# SCH.net
KiCad netlist of a schematic drawn in Altium Designer
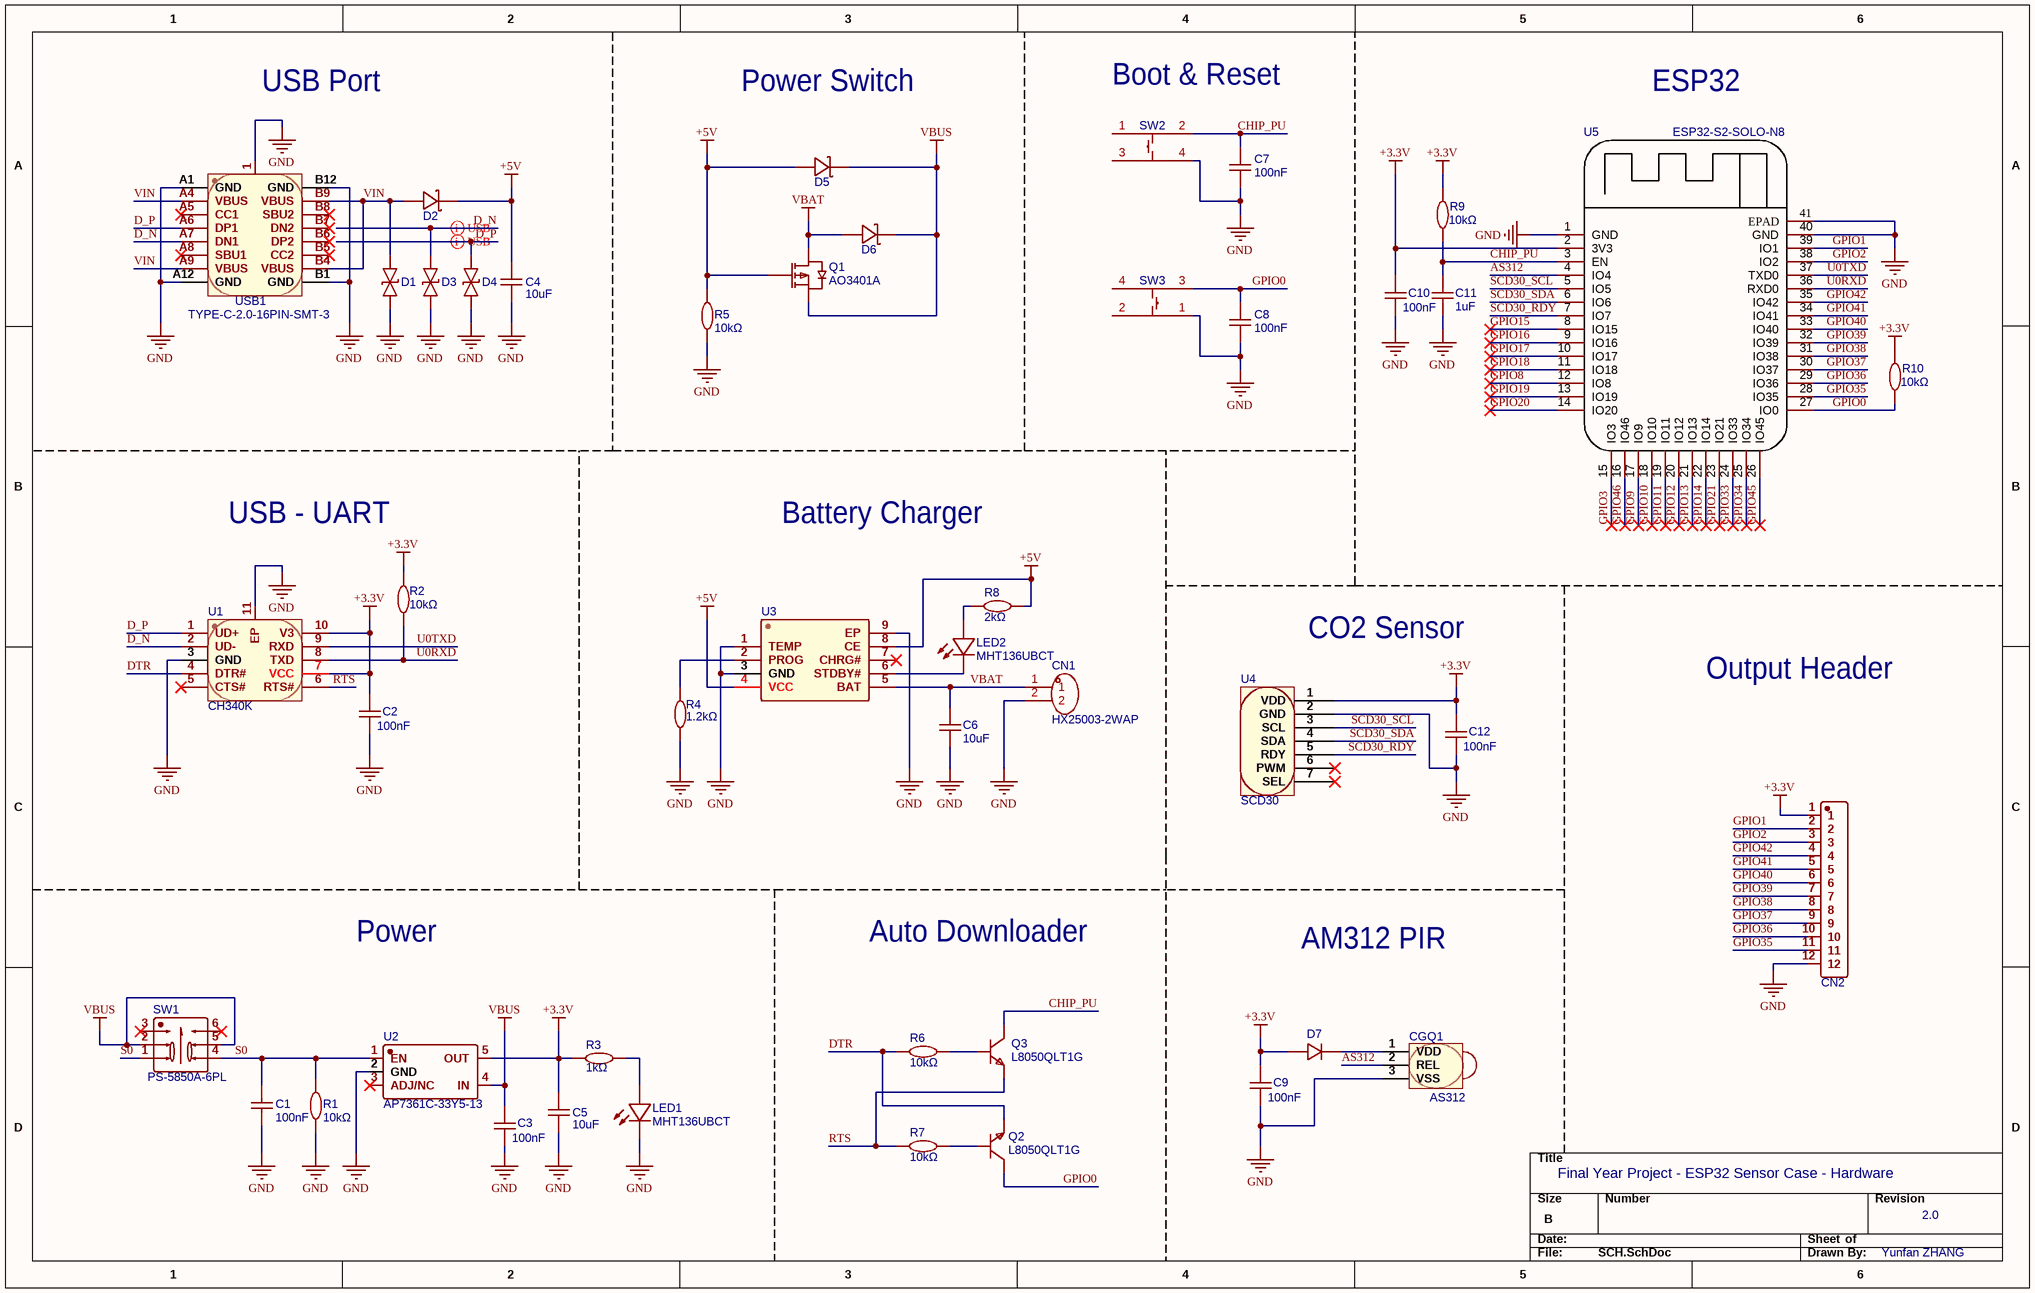
[diagram p0: SCH.SchDoc]

(export (version "E")
  (design (tool "Eeschema 10.0.6"))
  (components
    (comp (ref "C1")
      (value "100nF")
      (footprint "C0603")
      (description "容值:100nF;精度:±10%;额定电压:50V;材质(温度系数):X7R;")
      (fields
        (field (name "MANUFACTURER") "YAGEO(国巨)")
        (field (name "MANUFACTURER PART") "CC0603KRX7R9BB104")
      )
      (libsource (lib "Sensor_Board") (part "C 100nF 0603 - CC0603KRX7R9BB104"))
    )
    (comp (ref "C2")
      (value "100nF")
      (footprint "C0603")
      (description "容值:100nF;精度:±10%;额定电压:50V;材质(温度系数):X7R;")
      (fields
        (field (name "MANUFACTURER") "YAGEO(国巨)")
        (field (name "MANUFACTURER PART") "CC0603KRX7R9BB104")
        (field (name "NAME") "100nF")
      )
      (libsource (lib "Sensor_Board") (part "C 100nF 0603 - CC0603KRX7R9BB104"))
    )
    (comp (ref "C3")
      (value "100nF")
      (footprint "C0603")
      (description "容值:100nF;精度:±10%;额定电压:50V;材质(温度系数):X7R;")
      (fields
        (field (name "MANUFACTURER") "YAGEO(国巨)")
        (field (name "MANUFACTURER PART") "CC0603KRX7R9BB104")
        (field (name "NAME") "100nF")
      )
      (libsource (lib "Sensor_Board") (part "C 100nF 0603 - CC0603KRX7R9BB104"))
    )
    (comp (ref "C4")
      (value "10uF")
      (footprint "C0805")
      (description "容值:10uF;精度:±10%;额定电压:25V;材质(温度系数):X5R;")
      (fields
        (field (name "MANUFACTURER") "YAGEO(国巨)")
        (field (name "MANUFACTURER PART") "CC0805KKX5R8BB106")
        (field (name "NAME") "10uF")
      )
      (libsource (lib "Sensor_Board") (part "C 10uF 0805 - CC0805KKX5R8BB106"))
    )
    (comp (ref "C5")
      (value "10uF")
      (footprint "C0805")
      (description "容值:10uF;精度:±10%;额定电压:25V;材质(温度系数):X5R;")
      (fields
        (field (name "MANUFACTURER") "YAGEO(国巨)")
        (field (name "MANUFACTURER PART") "CC0805KKX5R8BB106")
        (field (name "NAME") "10uF")
      )
      (libsource (lib "Sensor_Board") (part "C 10uF 0805 - CC0805KKX5R8BB106"))
    )
    (comp (ref "C6")
      (value "10uF")
      (footprint "C0805")
      (description "容值:10uF;精度:±10%;额定电压:25V;材质(温度系数):X5R;")
      (fields
        (field (name "MANUFACTURER") "YAGEO(国巨)")
        (field (name "MANUFACTURER PART") "CC0805KKX5R8BB106")
      )
      (libsource (lib "Sensor_Board") (part "C 10uF 0805 - CC0805KKX5R8BB106"))
    )
    (comp (ref "C7")
      (value "100nF")
      (footprint "C0603")
      (description "容值:100nF;精度:±10%;额定电压:50V;材质(温度系数):X7R;")
      (fields
        (field (name "MANUFACTURER") "YAGEO(国巨)")
        (field (name "MANUFACTURER PART") "CC0603KRX7R9BB104")
      )
      (libsource (lib "Sensor_Board") (part "C 100nF 0603 - CC0603KRX7R9BB104"))
    )
    (comp (ref "C8")
      (value "100nF")
      (footprint "C0603")
      (description "容值:100nF;精度:±10%;额定电压:50V;材质(温度系数):X7R;")
      (fields
        (field (name "MANUFACTURER") "YAGEO(国巨)")
        (field (name "MANUFACTURER PART") "CC0603KRX7R9BB104")
      )
      (libsource (lib "Sensor_Board") (part "C 100nF 0603 - CC0603KRX7R9BB104"))
    )
    (comp (ref "C9")
      (value "100nF")
      (footprint "C0603")
      (description "容值:100nF;精度:±10%;额定电压:50V;材质(温度系数):X7R;")
      (fields
        (field (name "MANUFACTURER") "YAGEO(国巨)")
        (field (name "MANUFACTURER PART") "CC0603KRX7R9BB104")
        (field (name "NAME") "100nF")
      )
      (libsource (lib "Sensor_Board") (part "C 100nF 0603 - CC0603KRX7R9BB104"))
    )
    (comp (ref "C10")
      (value "100nF")
      (footprint "C0603")
      (description "容值:100nF;精度:±10%;额定电压:50V;材质(温度系数):X7R;")
      (fields
        (field (name "MANUFACTURER") "YAGEO(国巨)")
        (field (name "MANUFACTURER PART") "CC0603KRX7R9BB104")
        (field (name "NAME") "100nF")
      )
      (libsource (lib "Sensor_Board") (part "C 100nF 0603 - CC0603KRX7R9BB104"))
    )
    (comp (ref "C11")
      (value "1uF")
      (footprint "C0603")
      (description "容值:1uF;精度:±10%;额定电压:25V;材质(温度系数):X5R;")
      (fields
        (field (name "MANUFACTURER") "YAGEO(国巨)")
        (field (name "MANUFACTURER PART") "CC0603KRX5R8BB105")
        (field (name "NAME") "1uF")
      )
      (libsource (lib "Sensor_Board") (part "C 1uF 0603 - CC0603KRX5R8BB105"))
    )
    (comp (ref "C12")
      (value "100nF")
      (footprint "C0603")
      (description "容值:100nF;精度:±10%;额定电压:50V;材质(温度系数):X7R;")
      (fields
        (field (name "MANUFACTURER") "YAGEO(国巨)")
        (field (name "MANUFACTURER PART") "CC0603KRX7R9BB104")
        (field (name "NAME") "100nF")
      )
      (libsource (lib "Sensor_Board") (part "C 100nF 0603 - CC0603KRX7R9BB104"))
    )
    (comp (ref "CGQ1")
      (value "AS312")
      (footprint "AS312")
      (description "直接数字信号输出智能人体热释电红外传感器")
      (fields (field (name "MANUFACTURER") "森霸"))
      (libsource (lib "Sensor_Board") (part "AS312"))
    )
    (comp (ref "CN1")
      (value "HX25003-2WAP")
      (footprint "Conn - XH2.54_2P_W")
      (description "参考系列:XH;间距:2.5mm;插针结构:1x2P;排数:1;每排PIN数:2;行距:-;公母:公型插针;安装方式:弯插;额定电流:-;工作温度范围:-;")
      (fields (field (name "MANUFACTURER") "HX(红星)"))
      (libsource (lib "Sensor_Board") (part "Conn - XH2.54_2P"))
    )
    (comp (ref "CN2")
      (value "X4611WV-12I-C28D40")
      (footprint "Conn - Header_P2.00mm_1*12p_V")
      (fields (field (name "MANUFACTURER") "XKB Connectivity(中国星坤)"))
      (libsource (lib "Sensor_Board") (part "Conn - Header_P2.00mm_1*12p"))
    )
    (comp (ref "D1")
      (value "LESD5D5.0CT1G")
      (footprint "SOD-523")
      (description "极性:Bidirectional;反向关断电压（典型值）:5V;击穿电压（最小值）:5.6V;箝位电压:18.6V;峰值脉冲电流（10/1000us）:9.4A (8/20us);")
      (fields (field (name "MANUFACTURER") "LRC(乐山无线电)"))
      (libsource (lib "Sensor_Board") (part "D - LESD5D5.0CT1G"))
    )
    (comp (ref "D2")
      (value "1N5819HW-7-F")
      (footprint "SOD-123")
      (description "直流反向耐压(Vr):40V;平均整流电流(Io):1A;正向压降(Vf):450mV@1A;")
      (fields (field (name "MANUFACTURER") "DIODES(美台)"))
      (libsource (lib "Sensor_Board") (part "D - 1N5819HW-7-F"))
    )
    (comp (ref "D3")
      (value "LESD5D5.0CT1G")
      (footprint "SOD-523")
      (description "极性:Bidirectional;反向关断电压（典型值）:5V;击穿电压（最小值）:5.6V;箝位电压:18.6V;峰值脉冲电流（10/1000us）:9.4A (8/20us);")
      (fields (field (name "MANUFACTURER") "LRC(乐山无线电)"))
      (libsource (lib "Sensor_Board") (part "D - LESD5D5.0CT1G"))
    )
    (comp (ref "D4")
      (value "LESD5D5.0CT1G")
      (footprint "SOD-523")
      (description "极性:Bidirectional;反向关断电压（典型值）:5V;击穿电压（最小值）:5.6V;箝位电压:18.6V;峰值脉冲电流（10/1000us）:9.4A (8/20us);")
      (fields (field (name "MANUFACTURER") "LRC(乐山无线电)"))
      (libsource (lib "Sensor_Board") (part "D - LESD5D5.0CT1G"))
    )
    (comp (ref "D5")
      (value "1N5819HW-7-F")
      (footprint "SOD-123")
      (description "直流反向耐压(Vr):40V;平均整流电流(Io):1A;正向压降(Vf):450mV@1A;")
      (fields (field (name "MANUFACTURER") "DIODES(美台)"))
      (libsource (lib "Sensor_Board") (part "D - 1N5819HW-7-F"))
    )
    (comp (ref "D6")
      (value "1N5819HW-7-F")
      (footprint "SOD-123")
      (description "直流反向耐压(Vr):40V;平均整流电流(Io):1A;正向压降(Vf):450mV@1A;")
      (fields (field (name "MANUFACTURER") "DIODES(美台)"))
      (libsource (lib "Sensor_Board") (part "D - 1N5819HW-7-F"))
    )
    (comp (ref "D7")
      (value "CUS08F30,H3F")
      (footprint "SOD-323F")
      (description "直流反向耐压(Vr):30V;平均整流电流(Io):800mA;正向压降(Vf):220mV@10mA;")
      (fields (field (name "MANUFACTURER") "TOSHIBA(东芝)"))
      (libsource (lib "Sensor_Board") (part "D - CUS08F30,H3F"))
    )
    (comp (ref "LED1")
      (value "anufacturer Part")
      (footprint "LED0402")
      (fields
        (field (name "MANUFACTURER") "MEIHUA(美华)")
        (field (name "MANUFACTURER PART") "MHT136UBCT")
        (field (name "NAME") "MHT136UBCT")
      )
      (libsource (lib "Sensor_Board") (part "LED - MHT136UBCT"))
    )
    (comp (ref "LED2")
      (value "anufacturer Part")
      (footprint "LED0402")
      (fields
        (field (name "MANUFACTURER") "MEIHUA(美华)")
        (field (name "MANUFACTURER PART") "MHT136UBCT")
        (field (name "NAME") "MHT136UBCT")
      )
      (libsource (lib "Sensor_Board") (part "LED - MHT136UBCT"))
    )
    (comp (ref "Q1")
      (value "AO3401A")
      (footprint "SOT-23")
      (fields (field (name "MANUFACTURER") "AOS") (field (name "NAME") "AO3401A"))
      (libsource (lib "Sensor_Board") (part "PMOS - AO3401A_C15127"))
    )
    (comp (ref "Q2")
      (value "L8050QLT1G")
      (footprint "SOT-23-3")
      (description "晶体管类型:NPN;集射极击穿电压(Vceo):25V;集电极电流(Ic):800mA;功率(Pd):225mW;")
      (fields (field (name "MANUFACTURER") "LRC(乐山无线电)") (field (name "NAME") "L8050QLT1G"))
      (libsource (lib "Sensor_Board") (part "NPN - L8050QLT1G"))
    )
    (comp (ref "Q3")
      (value "L8050QLT1G")
      (footprint "SOT-23-3")
      (description "晶体管类型:NPN;集射极击穿电压(Vceo):25V;集电极电流(Ic):800mA;功率(Pd):225mW;")
      (fields (field (name "MANUFACTURER") "LRC(乐山无线电)") (field (name "NAME") "L8050QLT1G"))
      (libsource (lib "Sensor_Board") (part "NPN - L8050QLT1G"))
    )
    (comp (ref "R1")
      (value "10kΩ")
      (footprint "R0603")
      (description "电阻类型:厚膜电阻;阻值:10kΩ;精度:±1%;功率:100mW;温度系数:±100ppm/;最大工作电压:75V;工作温度范围:-55~+155;")
      (fields (field (name "MANUFACTURER") "YAGEO(国巨)") (field (name "MANUFACTURER PART") "AC0603FR-0710KL"))
      (libsource (lib "Sensor_Board") (part "R 10K 0603 - AC0603FR-0710KL"))
    )
    (comp (ref "R2")
      (value "10kΩ")
      (footprint "R0603")
      (description "电阻类型:厚膜电阻;阻值:10kΩ;精度:±1%;功率:100mW;温度系数:±100ppm/;最大工作电压:75V;工作温度范围:-55~+155;")
      (fields (field (name "MANUFACTURER") "YAGEO(国巨)") (field (name "MANUFACTURER PART") "AC0603FR-0710KL"))
      (libsource (lib "Sensor_Board") (part "R 10K 0603 - AC0603FR-0710KL"))
    )
    (comp (ref "R3")
      (value "1kΩ")
      (footprint "R0603")
      (description "电阻类型:厚膜电阻;阻值:1kΩ;精度:±0.5%;功率:100mW;温度系数:±100ppm/;最大工作电压:75V;工作温度范围:-55~+155;")
      (fields (field (name "MANUFACTURER") "YAGEO(国巨)") (field (name "MANUFACTURER PART") "RC0603DR-071KL"))
      (libsource (lib "Sensor_Board") (part "R 1K 0603 - RC0603DR-071KL"))
    )
    (comp (ref "R4")
      (value "1.2kΩ")
      (footprint "R0603")
      (description "电阻类型:厚膜电阻;阻值:1.2kΩ;精度:±1%;功率:100mW;温度系数:±100ppm/;最大工作电压:75V;工作温度范围:-55~+155;")
      (fields (field (name "MANUFACTURER") "YAGEO(国巨)") (field (name "MANUFACTURER PART") "RC0603FR-071K2L"))
      (libsource (lib "Sensor_Board") (part "R 1.2K 0603 - RC0603FR-071K2L"))
    )
    (comp (ref "R5")
      (value "10kΩ")
      (footprint "R0603")
      (description "电阻类型:厚膜电阻;阻值:10kΩ;精度:±1%;功率:100mW;温度系数:±100ppm/;最大工作电压:75V;工作温度范围:-55~+155;")
      (fields (field (name "MANUFACTURER") "YAGEO(国巨)") (field (name "MANUFACTURER PART") "AC0603FR-0710KL"))
      (libsource (lib "Sensor_Board") (part "R 10K 0603 - AC0603FR-0710KL"))
    )
    (comp (ref "R6")
      (value "10kΩ")
      (footprint "R0603")
      (description "电阻类型:厚膜电阻;阻值:10kΩ;精度:±1%;功率:100mW;温度系数:±100ppm/;最大工作电压:75V;工作温度范围:-55~+155;")
      (fields (field (name "MANUFACTURER") "YAGEO(国巨)") (field (name "MANUFACTURER PART") "AC0603FR-0710KL"))
      (libsource (lib "Sensor_Board") (part "R 10K 0603 - AC0603FR-0710KL"))
    )
    (comp (ref "R7")
      (value "10kΩ")
      (footprint "R0603")
      (description "电阻类型:厚膜电阻;阻值:10kΩ;精度:±1%;功率:100mW;温度系数:±100ppm/;最大工作电压:75V;工作温度范围:-55~+155;")
      (fields (field (name "MANUFACTURER") "YAGEO(国巨)") (field (name "MANUFACTURER PART") "AC0603FR-0710KL"))
      (libsource (lib "Sensor_Board") (part "R 10K 0603 - AC0603FR-0710KL"))
    )
    (comp (ref "R8")
      (value "2kΩ")
      (footprint "R0603")
      (description "精度:±1%;阻值:2kΩ;温度系数:±100ppm/;功率:100mW;最大工作电压:75V;工作温度范围:-55~+155;")
      (fields (field (name "MANUFACTURER") "YAGEO(国巨)") (field (name "MANUFACTURER PART") "RC0603FR-072KL"))
      (libsource (lib "Sensor_Board") (part "R 2K 0603 - RC0603FR-072KL"))
    )
    (comp (ref "R9")
      (value "10kΩ")
      (footprint "R0603")
      (description "电阻类型:厚膜电阻;阻值:10kΩ;精度:±1%;功率:100mW;温度系数:±100ppm/;最大工作电压:75V;工作温度范围:-55~+155;")
      (fields (field (name "MANUFACTURER") "YAGEO(国巨)") (field (name "MANUFACTURER PART") "AC0603FR-0710KL"))
      (libsource (lib "Sensor_Board") (part "R 10K 0603 - AC0603FR-0710KL"))
    )
    (comp (ref "R10")
      (value "10kΩ")
      (footprint "R0603")
      (description "电阻类型:厚膜电阻;阻值:10kΩ;精度:±1%;功率:100mW;温度系数:±100ppm/;最大工作电压:75V;工作温度范围:-55~+155;")
      (fields (field (name "MANUFACTURER") "YAGEO(国巨)") (field (name "MANUFACTURER PART") "AC0603FR-0710KL"))
      (libsource (lib "Sensor_Board") (part "R 10K 0603 - AC0603FR-0710KL"))
    )
    (comp (ref "SW1")
      (value "PS-5850A-6PL")
      (footprint "SW-TH_6P-L5.8-W5.8")
      (description "5.8自锁按键开关 高头 耐高温")
      (fields (field (name "MANUFACTURER") "G-Switch(品赞)"))
      (libsource (lib "Sensor_Board") (part "SW - PS-5850A-6PL"))
    )
    (comp (ref "SW2")
      (value "TD-1150SR-3.8H-250")
      (footprint "SW-PB_SMD_L4.5W4.5")
      (fields (field (name "MANUFACTURER") "DEALON(德艺隆)"))
      (libsource (lib "Sensor_Board") (part "SW - TD-1150SR-3.8H-250"))
    )
    (comp (ref "SW3")
      (value "TD-1150SR-3.8H-250")
      (footprint "SW-PB_SMD_L4.5W4.5")
      (fields (field (name "MANUFACTURER") "DEALON(德艺隆)"))
      (libsource (lib "Sensor_Board") (part "SW - TD-1150SR-3.8H-250"))
    )
    (comp (ref "U1")
      (value "CH340K")
      (footprint "ESOP-10")
      (description "类型:-;协议类别:-;驱动器/接收器数:-;数据速率:-;")
      (fields (field (name "MANUFACTURER") "WCH(南京沁恒)"))
      (libsource (lib "Sensor_Board") (part "CH340K"))
    )
    (comp (ref "U2")
      (value "AP7361C-33Y5-13")
      (footprint "SOT-89-5")
      (fields (field (name "MANUFACTURER") "DIODES(美台)"))
      (libsource (lib "Sensor_Board") (part "AP7361C-33Y5-13"))
    )
    (comp (ref "U3")
      (value "TP4056")
      (footprint "ESOP-8")
      (fields (field (name "MANUFACTURER") "UMW(友台半导体)"))
      (libsource (lib "Sensor_Board") (part "TP4056"))
    )
    (comp (ref "U4")
      (value "SCD30")
      (footprint "SCD30")
      (description "SEL: Pull to VDD - ModBus ¦ Down to GND - I2C")
      (libsource (lib "Sensor_Board") (part "SCD30"))
    )
    (comp (ref "U5")
      (value "ESP32-S2-SOLO-N8")
      (footprint "ESP32-S2-SOLO")
      (fields (field (name "MANUFACTURER") "ESPRESSIF 乐鑫") (field (name "NAME") "ESP32-S2-SOLO-N8"))
      (libsource (lib "Sensor_Board") (part "ESP32-S2-SOLO-N8"))
    )
    (comp (ref "USB1")
      (value "TYPE-C-2.0-16PIN-SMT-3")
      (footprint "TYPE-C-SMD_TYPE-CF3.1")
      (description "连接器类型:Type-C;标准:USB 2.0;公母:母座;触点数量:16;端口数量:1;安装方式:卧贴;额定电流 - 电源:3A;工作温度范围:-40~+85;")
      (fields (field (name "MANUFACTURER") "CIKI(皓富)") (field (name "NAME") "TYPE-C-2.0-16PIN-SMT-3"))
      (libsource (lib "Sensor_Board") (part "USB - TYPE-C-2.0-16PIN-SMT-3"))
    )
  )
  (nets
    (net (code "1") (name "+3.3V") (class "Default")
      (node (ref "C10") (pin "2") (pinfunction "2_2") (pintype "passive"))
      (node (ref "C12") (pin "2") (pinfunction "2_2") (pintype "passive"))
      (node (ref "C2") (pin "2") (pinfunction "2_2") (pintype "passive"))
      (node (ref "C5") (pin "1") (pinfunction "1_1") (pintype "passive"))
      (node (ref "C9") (pin "2") (pinfunction "2_2") (pintype "passive"))
      (node (ref "CN2") (pin "1") (pinfunction "1_1") (pintype "passive"))
      (node (ref "D7") (pin "2") (pinfunction "A_2") (pintype "passive"))
      (node (ref "R10") (pin "2") (pinfunction "2_2") (pintype "passive"))
      (node (ref "R2") (pin "2") (pinfunction "2_2") (pintype "passive"))
      (node (ref "R3") (pin "1") (pinfunction "1_1") (pintype "passive"))
      (node (ref "R9") (pin "2") (pinfunction "2_2") (pintype "passive"))
      (node (ref "U1") (pin "10") (pinfunction "V3_10") (pintype "passive"))
      (node (ref "U1") (pin "7") (pinfunction "VCC_7") (pintype "passive"))
      (node (ref "U2") (pin "5") (pinfunction "OUT_5") (pintype "passive"))
      (node (ref "U4") (pin "1") (pinfunction "VDD_1") (pintype "passive"))
      (node (ref "U5") (pin "2") (pinfunction "3V3_2") (pintype "passive"))
    )
    (net (code "2") (name "+5V") (class "Default")
      (node (ref "C4") (pin "1") (pinfunction "1_1") (pintype "passive"))
      (node (ref "D2") (pin "2") (pinfunction "K_2") (pintype "passive"))
      (node (ref "D5") (pin "1") (pinfunction "A_1") (pintype "passive"))
      (node (ref "Q1") (pin "1") (pinfunction "G_1") (pintype "passive"))
      (node (ref "R5") (pin "2") (pinfunction "2_2") (pintype "passive"))
      (node (ref "R8") (pin "2") (pinfunction "2_2") (pintype "passive"))
      (node (ref "U3") (pin "4") (pinfunction "VCC_4") (pintype "passive"))
      (node (ref "U3") (pin "8") (pinfunction "CE_8") (pintype "passive"))
    )
    (net (code "3") (name "/AS312") (class "Default")
      (node (ref "CGQ1") (pin "2") (pinfunction "REL_2") (pintype "passive"))
      (node (ref "U5") (pin "4") (pinfunction "IO4_4") (pintype "passive"))
    )
    (net (code "4") (name "/CHIP_PU") (class "Default")
      (node (ref "C11") (pin "2") (pinfunction "2_2") (pintype "passive"))
      (node (ref "C7") (pin "2") (pinfunction "2_2") (pintype "passive"))
      (node (ref "Q3") (pin "3") (pinfunction "C_3") (pintype "passive"))
      (node (ref "R9") (pin "1") (pinfunction "1_1") (pintype "passive"))
      (node (ref "SW2") (pin "2") (pinfunction "2_2") (pintype "passive"))
      (node (ref "U5") (pin "3") (pinfunction "EN_3") (pintype "passive"))
    )
    (net (code "5") (name "/DTR") (class "Default")
      (node (ref "Q2") (pin "2") (pinfunction "E_2") (pintype "passive"))
      (node (ref "R6") (pin "1") (pinfunction "1_1") (pintype "passive"))
      (node (ref "U1") (pin "4") (pinfunction "DTR#_4") (pintype "passive"))
    )
    (net (code "6") (name "/D_N") (class "Default")
      (node (ref "D3") (pin "2") (pinfunction "2_2") (pintype "passive"))
      (node (ref "U1") (pin "2") (pinfunction "UD-_2") (pintype "passive"))
      (node (ref "USB1") (pin "A7") (pinfunction "DN1_A7") (pintype "passive"))
    )
    (net (code "7") (name "/D_P") (class "Default")
      (node (ref "D4") (pin "2") (pinfunction "2_2") (pintype "passive"))
      (node (ref "U1") (pin "1") (pinfunction "UD+_1") (pintype "passive"))
      (node (ref "USB1") (pin "A6") (pinfunction "DP1_A6") (pintype "passive"))
    )
    (net (code "8") (name "/GPIO0") (class "Default")
      (node (ref "C8") (pin "2") (pinfunction "2_2") (pintype "passive"))
      (node (ref "Q2") (pin "3") (pinfunction "C_3") (pintype "passive"))
      (node (ref "R10") (pin "1") (pinfunction "1_1") (pintype "passive"))
      (node (ref "SW3") (pin "3") (pinfunction "3_3") (pintype "passive"))
      (node (ref "U5") (pin "27") (pinfunction "IO0_27") (pintype "passive"))
    )
    (net (code "9") (name "/GPIO1") (class "Default")
      (node (ref "CN2") (pin "2") (pinfunction "2_2") (pintype "passive"))
      (node (ref "U5") (pin "39") (pinfunction "IO1_39") (pintype "passive"))
    )
    (net (code "10") (name "/GPIO2") (class "Default")
      (node (ref "CN2") (pin "3") (pinfunction "3_3") (pintype "passive"))
      (node (ref "U5") (pin "38") (pinfunction "IO2_38") (pintype "passive"))
    )
    (net (code "11") (name "/GPIO3") (class "Default")
      (node (ref "U5") (pin "15") (pinfunction "IO3_15") (pintype "passive+no_connect"))
    )
    (net (code "12") (name "/GPIO8") (class "Default")
      (node (ref "U5") (pin "12") (pinfunction "IO8_12") (pintype "passive+no_connect"))
    )
    (net (code "13") (name "/GPIO9") (class "Default")
      (node (ref "U5") (pin "17") (pinfunction "IO9_17") (pintype "passive+no_connect"))
    )
    (net (code "14") (name "/GPIO10") (class "Default")
      (node (ref "U5") (pin "18") (pinfunction "IO10_18") (pintype "passive+no_connect"))
    )
    (net (code "15") (name "/GPIO11") (class "Default")
      (node (ref "U5") (pin "19") (pinfunction "IO11_19") (pintype "passive+no_connect"))
    )
    (net (code "16") (name "/GPIO12") (class "Default")
      (node (ref "U5") (pin "20") (pinfunction "IO12_20") (pintype "passive+no_connect"))
    )
    (net (code "17") (name "/GPIO13") (class "Default")
      (node (ref "U5") (pin "21") (pinfunction "IO13_21") (pintype "passive+no_connect"))
    )
    (net (code "18") (name "/GPIO14") (class "Default")
      (node (ref "U5") (pin "22") (pinfunction "IO14_22") (pintype "passive+no_connect"))
    )
    (net (code "19") (name "/GPIO15") (class "Default")
      (node (ref "U5") (pin "8") (pinfunction "IO15_8") (pintype "passive+no_connect"))
    )
    (net (code "20") (name "/GPIO16") (class "Default")
      (node (ref "U5") (pin "9") (pinfunction "IO16_9") (pintype "passive+no_connect"))
    )
    (net (code "21") (name "/GPIO17") (class "Default")
      (node (ref "U5") (pin "10") (pinfunction "IO17_10") (pintype "passive+no_connect"))
    )
    (net (code "22") (name "/GPIO18") (class "Default")
      (node (ref "U5") (pin "11") (pinfunction "IO18_11") (pintype "passive+no_connect"))
    )
    (net (code "23") (name "/GPIO19") (class "Default")
      (node (ref "U5") (pin "13") (pinfunction "IO19_13") (pintype "passive+no_connect"))
    )
    (net (code "24") (name "/GPIO20") (class "Default")
      (node (ref "U5") (pin "14") (pinfunction "IO20_14") (pintype "passive+no_connect"))
    )
    (net (code "25") (name "/GPIO21") (class "Default")
      (node (ref "U5") (pin "23") (pinfunction "IO21_23") (pintype "passive+no_connect"))
    )
    (net (code "26") (name "/GPIO33") (class "Default")
      (node (ref "U5") (pin "24") (pinfunction "IO33_24") (pintype "passive+no_connect"))
    )
    (net (code "27") (name "/GPIO34") (class "Default")
      (node (ref "U5") (pin "25") (pinfunction "IO34_25") (pintype "passive+no_connect"))
    )
    (net (code "28") (name "/GPIO35") (class "Default")
      (node (ref "CN2") (pin "11") (pinfunction "11_11") (pintype "passive"))
      (node (ref "U5") (pin "28") (pinfunction "IO35_28") (pintype "passive"))
    )
    (net (code "29") (name "/GPIO36") (class "Default")
      (node (ref "CN2") (pin "10") (pinfunction "10_10") (pintype "passive"))
      (node (ref "U5") (pin "29") (pinfunction "IO36_29") (pintype "passive"))
    )
    (net (code "30") (name "/GPIO37") (class "Default")
      (node (ref "CN2") (pin "9") (pinfunction "9_9") (pintype "passive"))
      (node (ref "U5") (pin "30") (pinfunction "IO37_30") (pintype "passive"))
    )
    (net (code "31") (name "/GPIO38") (class "Default")
      (node (ref "CN2") (pin "8") (pinfunction "8_8") (pintype "passive"))
      (node (ref "U5") (pin "31") (pinfunction "IO38_31") (pintype "passive"))
    )
    (net (code "32") (name "/GPIO39") (class "Default")
      (node (ref "CN2") (pin "7") (pinfunction "7_7") (pintype "passive"))
      (node (ref "U5") (pin "32") (pinfunction "IO39_32") (pintype "passive"))
    )
    (net (code "33") (name "/GPIO40") (class "Default")
      (node (ref "CN2") (pin "6") (pinfunction "6_6") (pintype "passive"))
      (node (ref "U5") (pin "33") (pinfunction "IO40_33") (pintype "passive"))
    )
    (net (code "34") (name "/GPIO41") (class "Default")
      (node (ref "CN2") (pin "5") (pinfunction "5_5") (pintype "passive"))
      (node (ref "U5") (pin "34") (pinfunction "IO41_34") (pintype "passive"))
    )
    (net (code "35") (name "/GPIO42") (class "Default")
      (node (ref "CN2") (pin "4") (pinfunction "4_4") (pintype "passive"))
      (node (ref "U5") (pin "35") (pinfunction "IO42_35") (pintype "passive"))
    )
    (net (code "36") (name "/GPIO45") (class "Default")
      (node (ref "U5") (pin "26") (pinfunction "IO45_26") (pintype "passive+no_connect"))
    )
    (net (code "37") (name "/GPIO46") (class "Default")
      (node (ref "U5") (pin "16") (pinfunction "IO46_16") (pintype "passive+no_connect"))
    )
    (net (code "38") (name "/RTS") (class "Default")
      (node (ref "Q3") (pin "2") (pinfunction "E_2") (pintype "passive"))
      (node (ref "R7") (pin "1") (pinfunction "1_1") (pintype "passive"))
      (node (ref "U1") (pin "6") (pinfunction "RTS#_6") (pintype "passive"))
    )
    (net (code "39") (name "/S0") (class "Default")
      (node (ref "C1") (pin "2") (pinfunction "2_2") (pintype "passive"))
      (node (ref "R1") (pin "2") (pinfunction "2_2") (pintype "passive"))
      (node (ref "SW1") (pin "1") (pinfunction "1_1") (pintype "passive"))
      (node (ref "SW1") (pin "4") (pinfunction "4_4") (pintype "passive"))
      (node (ref "U2") (pin "1") (pinfunction "EN_1") (pintype "passive"))
    )
    (net (code "40") (name "/SCD30_RDY") (class "Default")
      (node (ref "U4") (pin "5") (pinfunction "RDY_5") (pintype "passive"))
      (node (ref "U5") (pin "7") (pinfunction "IO7_7") (pintype "passive"))
    )
    (net (code "41") (name "/SCD30_SCL") (class "Default")
      (node (ref "U4") (pin "3") (pinfunction "SCL_3") (pintype "passive"))
      (node (ref "U5") (pin "5") (pinfunction "IO5_5") (pintype "passive"))
    )
    (net (code "42") (name "/SCD30_SDA") (class "Default")
      (node (ref "U4") (pin "4") (pinfunction "SDA_4") (pintype "passive"))
      (node (ref "U5") (pin "6") (pinfunction "IO6_6") (pintype "passive"))
    )
    (net (code "43") (name "/U0RXD") (class "Default")
      (node (ref "R2") (pin "1") (pinfunction "1_1") (pintype "passive"))
      (node (ref "U1") (pin "8") (pinfunction "TXD_8") (pintype "passive"))
      (node (ref "U5") (pin "36") (pinfunction "RXD0_36") (pintype "passive"))
    )
    (net (code "44") (name "/U0TXD") (class "Default")
      (node (ref "U1") (pin "9") (pinfunction "RXD_9") (pintype "passive"))
      (node (ref "U5") (pin "37") (pinfunction "TXD0_37") (pintype "passive"))
    )
    (net (code "45") (name "/VIN") (class "Default")
      (node (ref "D1") (pin "2") (pinfunction "2_2") (pintype "passive"))
      (node (ref "D2") (pin "1") (pinfunction "A_1") (pintype "passive"))
      (node (ref "USB1") (pin "A4") (pinfunction "VBUS_A4") (pintype "passive"))
      (node (ref "USB1") (pin "A9") (pinfunction "VBUS_A9") (pintype "passive"))
      (node (ref "USB1") (pin "B4") (pinfunction "VBUS_B4") (pintype "passive"))
      (node (ref "USB1") (pin "B9") (pinfunction "VBUS_B9") (pintype "passive"))
    )
    (net (code "46") (name "GND") (class "Default")
      (node (ref "C1") (pin "1") (pinfunction "1_1") (pintype "passive"))
      (node (ref "C10") (pin "1") (pinfunction "1_1") (pintype "passive"))
      (node (ref "C11") (pin "1") (pinfunction "1_1") (pintype "passive"))
      (node (ref "C12") (pin "1") (pinfunction "1_1") (pintype "passive"))
      (node (ref "C2") (pin "1") (pinfunction "1_1") (pintype "passive"))
      (node (ref "C3") (pin "1") (pinfunction "1_1") (pintype "passive"))
      (node (ref "C4") (pin "2") (pinfunction "2_2") (pintype "passive"))
      (node (ref "C5") (pin "2") (pinfunction "2_2") (pintype "passive"))
      (node (ref "C6") (pin "1") (pinfunction "1_1") (pintype "passive"))
      (node (ref "C7") (pin "1") (pinfunction "1_1") (pintype "passive"))
      (node (ref "C8") (pin "1") (pinfunction "1_1") (pintype "passive"))
      (node (ref "C9") (pin "1") (pinfunction "1_1") (pintype "passive"))
      (node (ref "CGQ1") (pin "3") (pinfunction "VSS_3") (pintype "passive"))
      (node (ref "CN1") (pin "2") (pinfunction "2_2") (pintype "passive"))
      (node (ref "CN2") (pin "12") (pinfunction "12_12") (pintype "passive"))
      (node (ref "D1") (pin "1") (pinfunction "1_1") (pintype "passive"))
      (node (ref "D3") (pin "1") (pinfunction "1_1") (pintype "passive"))
      (node (ref "D4") (pin "1") (pinfunction "1_1") (pintype "passive"))
      (node (ref "LED1") (pin "1") (pinfunction "K_1") (pintype "passive"))
      (node (ref "R1") (pin "1") (pinfunction "1_1") (pintype "passive"))
      (node (ref "R4") (pin "1") (pinfunction "1_1") (pintype "passive"))
      (node (ref "R5") (pin "1") (pinfunction "1_1") (pintype "passive"))
      (node (ref "SW2") (pin "4") (pinfunction "4_4") (pintype "passive"))
      (node (ref "SW3") (pin "1") (pinfunction "1_1") (pintype "passive"))
      (node (ref "U1") (pin "11") (pinfunction "EP_11") (pintype "passive"))
      (node (ref "U1") (pin "3") (pinfunction "GND_3") (pintype "passive"))
      (node (ref "U2") (pin "2") (pinfunction "GND_2") (pintype "passive"))
      (node (ref "U3") (pin "1") (pinfunction "TEMP_1") (pintype "passive"))
      (node (ref "U3") (pin "3") (pinfunction "GND_3") (pintype "passive"))
      (node (ref "U3") (pin "9") (pinfunction "EP_9") (pintype "passive"))
      (node (ref "U4") (pin "2") (pinfunction "GND_2") (pintype "passive"))
      (node (ref "U5") (pin "1") (pinfunction "GND_1") (pintype "passive"))
      (node (ref "U5") (pin "40") (pinfunction "GND_40") (pintype "passive"))
      (node (ref "U5") (pin "41") (pinfunction "EPAD_41") (pintype "passive"))
      (node (ref "USB1") (pin "1") (pinfunction "EH_1") (pintype "passive"))
      (node (ref "USB1") (pin "A1") (pinfunction "GND_A1") (pintype "passive"))
      (node (ref "USB1") (pin "A12") (pinfunction "GND_A12") (pintype "passive"))
      (node (ref "USB1") (pin "B1") (pinfunction "GND_B1") (pintype "passive"))
      (node (ref "USB1") (pin "B12") (pinfunction "GND_B12") (pintype "passive"))
    )
    (net (code "47") (name "Net-(CGQ1-VDD)") (class "Default")
      (node (ref "CGQ1") (pin "1") (pinfunction "VDD_1") (pintype "passive"))
      (node (ref "D7") (pin "1") (pinfunction "C_1") (pintype "passive"))
    )
    (net (code "48") (name "Net-(LED1-A)") (class "Default")
      (node (ref "LED1") (pin "2") (pinfunction "A_2") (pintype "passive"))
      (node (ref "R3") (pin "2") (pinfunction "2_2") (pintype "passive"))
    )
    (net (code "49") (name "Net-(LED2-A)") (class "Default")
      (node (ref "LED2") (pin "2") (pinfunction "A_2") (pintype "passive"))
      (node (ref "R8") (pin "1") (pinfunction "1_1") (pintype "passive"))
    )
    (net (code "50") (name "Net-(LED2-K)") (class "Default")
      (node (ref "LED2") (pin "1") (pinfunction "K_1") (pintype "passive"))
      (node (ref "U3") (pin "6") (pinfunction "STDBY#_6") (pintype "passive"))
    )
    (net (code "51") (name "Net-(Q2-B)") (class "Default")
      (node (ref "Q2") (pin "1") (pinfunction "B_1") (pintype "passive"))
      (node (ref "R7") (pin "2") (pinfunction "2_2") (pintype "passive"))
    )
    (net (code "52") (name "Net-(Q3-B)") (class "Default")
      (node (ref "Q3") (pin "1") (pinfunction "B_1") (pintype "passive"))
      (node (ref "R6") (pin "2") (pinfunction "2_2") (pintype "passive"))
    )
    (net (code "53") (name "Net-(U3-PROG)") (class "Default")
      (node (ref "R4") (pin "2") (pinfunction "2_2") (pintype "passive"))
      (node (ref "U3") (pin "2") (pinfunction "PROG_2") (pintype "passive"))
    )
    (net (code "54") (name "VBAT") (class "Default")
      (node (ref "C6") (pin "2") (pinfunction "2_2") (pintype "passive"))
      (node (ref "CN1") (pin "1") (pinfunction "1_1") (pintype "passive"))
      (node (ref "D6") (pin "1") (pinfunction "A_1") (pintype "passive"))
      (node (ref "Q1") (pin "3") (pinfunction "D_3") (pintype "passive"))
      (node (ref "U3") (pin "5") (pinfunction "BAT_5") (pintype "passive"))
    )
    (net (code "55") (name "VBUS") (class "Default")
      (node (ref "C3") (pin "2") (pinfunction "2_2") (pintype "passive"))
      (node (ref "D5") (pin "2") (pinfunction "K_2") (pintype "passive"))
      (node (ref "D6") (pin "2") (pinfunction "K_2") (pintype "passive"))
      (node (ref "Q1") (pin "2") (pinfunction "S_2") (pintype "passive"))
      (node (ref "SW1") (pin "2") (pinfunction "2_2") (pintype "passive"))
      (node (ref "SW1") (pin "5") (pinfunction "5_5") (pintype "passive"))
      (node (ref "U2") (pin "4") (pinfunction "IN_4") (pintype "passive"))
    )
    (net (code "56") (name "unconnected-(SW1-Pad3)") (class "Default")
      (node (ref "SW1") (pin "3") (pinfunction "3_3") (pintype "passive+no_connect"))
    )
    (net (code "57") (name "unconnected-(SW1-Pad6)") (class "Default")
      (node (ref "SW1") (pin "6") (pinfunction "6_6") (pintype "passive+no_connect"))
    )
    (net (code "58") (name "unconnected-(SW2-Pad1)") (class "Default")
      (node (ref "SW2") (pin "1") (pinfunction "1_1") (pintype "passive"))
    )
    (net (code "59") (name "unconnected-(SW2-Pad3)") (class "Default")
      (node (ref "SW2") (pin "3") (pinfunction "3_3") (pintype "passive"))
    )
    (net (code "60") (name "unconnected-(SW3-Pad2)") (class "Default")
      (node (ref "SW3") (pin "2") (pinfunction "2_2") (pintype "passive"))
    )
    (net (code "61") (name "unconnected-(SW3-Pad4)") (class "Default")
      (node (ref "SW3") (pin "4") (pinfunction "4_4") (pintype "passive"))
    )
    (net (code "62") (name "unconnected-(U1-CTS#-Pad5)") (class "Default")
      (node (ref "U1") (pin "5") (pinfunction "CTS#_5") (pintype "passive+no_connect"))
    )
    (net (code "63") (name "unconnected-(U2-ADJ{slash}NC-Pad3)") (class "Default")
      (node (ref "U2") (pin "3") (pinfunction "ADJ/NC_3") (pintype "passive+no_connect"))
    )
    (net (code "64") (name "unconnected-(U3-CHRG#-Pad7)") (class "Default")
      (node (ref "U3") (pin "7") (pinfunction "CHRG#_7") (pintype "passive+no_connect"))
    )
    (net (code "65") (name "unconnected-(U4-PWM-Pad6)") (class "Default")
      (node (ref "U4") (pin "6") (pinfunction "PWM_6") (pintype "passive+no_connect"))
    )
    (net (code "66") (name "unconnected-(U4-SEL-Pad7)") (class "Default")
      (node (ref "U4") (pin "7") (pinfunction "SEL_7") (pintype "passive+no_connect"))
    )
    (net (code "67") (name "unconnected-(USB1-CC1-PadA5)") (class "Default")
      (node (ref "USB1") (pin "A5") (pinfunction "CC1_A5") (pintype "passive+no_connect"))
    )
    (net (code "68") (name "unconnected-(USB1-CC2-PadB5)") (class "Default")
      (node (ref "USB1") (pin "B5") (pinfunction "CC2_B5") (pintype "passive+no_connect"))
    )
    (net (code "69") (name "unconnected-(USB1-DN2-PadB7)") (class "Default")
      (node (ref "USB1") (pin "B7") (pinfunction "DN2_B7") (pintype "passive+no_connect"))
    )
    (net (code "70") (name "unconnected-(USB1-DP2-PadB6)") (class "Default")
      (node (ref "USB1") (pin "B6") (pinfunction "DP2_B6") (pintype "passive+no_connect"))
    )
    (net (code "71") (name "unconnected-(USB1-SBU1-PadA8)") (class "Default")
      (node (ref "USB1") (pin "A8") (pinfunction "SBU1_A8") (pintype "passive+no_connect"))
    )
    (net (code "72") (name "unconnected-(USB1-SBU2-PadB8)") (class "Default")
      (node (ref "USB1") (pin "B8") (pinfunction "SBU2_B8") (pintype "passive+no_connect"))
    )
  )
)
